# Sheet1.net
KiCad netlist of a schematic drawn in Altium Designer
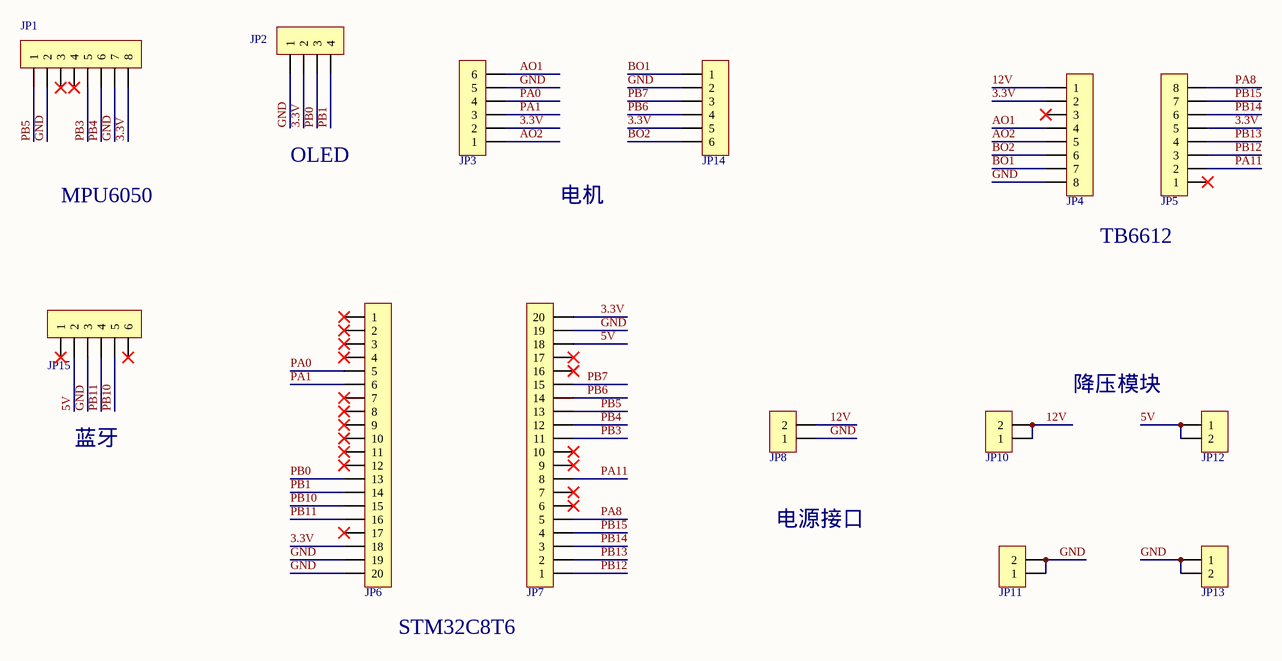
[diagram p0: Sheet1.SchDoc]

(export (version "E")
  (design (tool "Eeschema 10.0.6"))
  (components
    (comp (ref "JP1")
      (value "HDR-1X8")
      (footprint "HDR2.54-M-LI-8P")
      (description "8P接插件")
      (fields (field (name "版权归属") "封装库来自淘宝 ID：黄晶宝石"))
      (libsource (lib "5.3 - 接插件-脚距2.54 (100mil) ") (part "Header 8"))
    )
    (comp (ref "JP2")
      (value "HDR-1X4")
      (footprint "HDR2.54-M-LI-4P")
      (description "4P接插件")
      (fields (field (name "版权归属") "封装库来自淘宝 ID：黄晶宝石"))
      (libsource (lib "5.3 - 接插件-脚距2.54 (100mil) ") (part "Header 4"))
    )
    (comp (ref "JP3")
      (value "HDR-1X6")
      (footprint "HDR2.54-LI-6P")
      (description "6P接插件")
      (fields (field (name "版权归属") "封装库来自淘宝 ID：黄晶宝石"))
      (libsource (lib "5.3 - 接插件-脚距2.54 (100mil) ") (part "Header 6"))
    )
    (comp (ref "JP4")
      (value "HDR-1X8")
      (footprint "HDR2.54-M-LI-8P")
      (description "8P接插件")
      (fields (field (name "版权归属") "封装库来自淘宝 ID：黄晶宝石"))
      (libsource (lib "") (part "Header 8_2"))
    )
    (comp (ref "JP5")
      (value "HDR-1X8")
      (footprint "HDR2.54-M-LI-8P")
      (description "8P接插件")
      (fields (field (name "版权归属") "封装库来自淘宝 ID：黄晶宝石"))
      (libsource (lib "") (part "Header 8_1"))
    )
    (comp (ref "JP6")
      (value "HDR-1X20")
      (footprint "HDR2.54-M-LI-20P")
      (description "20P接插件")
      (fields (field (name "版权归属") "封装库来自淘宝 ID：黄晶宝石"))
      (libsource (lib "") (part "Header 20_1"))
    )
    (comp (ref "JP7")
      (value "HDR-1X20")
      (footprint "HDR2.54-M-LI-20P")
      (description "20P接插件")
      (fields (field (name "版权归属") "封装库来自淘宝 ID：黄晶宝石"))
      (libsource (lib "5.3 - 接插件-脚距2.54 (100mil) ") (part "Header 20"))
    )
    (comp (ref "JP8")
      (value "HDR-1X2")
      (footprint "HDR2.54-M-LI-2P")
      (description "2P接插件")
      (fields (field (name "版权归属") "封装库来自淘宝 ID：黄晶宝石"))
      (libsource (lib "5.3 - 接插件-脚距2.54 (100mil) ") (part "Header 2"))
    )
    (comp (ref "JP10")
      (value "HDR-1X2")
      (footprint "HDR2.54-M-LI-2P")
      (description "2P接插件")
      (fields (field (name "版权归属") "封装库来自淘宝 ID：黄晶宝石"))
      (libsource (lib "5.3 - 接插件-脚距2.54 (100mil) ") (part "Header 2"))
    )
    (comp (ref "JP11")
      (value "HDR-1X2")
      (footprint "HDR2.54-M-LI-2P")
      (description "2P接插件")
      (fields (field (name "版权归属") "封装库来自淘宝 ID：黄晶宝石"))
      (libsource (lib "5.3 - 接插件-脚距2.54 (100mil) ") (part "Header 2"))
    )
    (comp (ref "JP12")
      (value "HDR-1X2")
      (footprint "HDR2.54-M-LI-2P")
      (description "2P接插件")
      (fields (field (name "版权归属") "封装库来自淘宝 ID：黄晶宝石"))
      (libsource (lib "") (part "Header 2_1"))
    )
    (comp (ref "JP13")
      (value "HDR-1X2")
      (footprint "HDR2.54-M-LI-2P")
      (description "2P接插件")
      (fields (field (name "版权归属") "封装库来自淘宝 ID：黄晶宝石"))
      (libsource (lib "") (part "Header 2_1"))
    )
    (comp (ref "JP14")
      (value "HDR-1X6")
      (footprint "HDR2.54-LI-6P")
      (description "6P接插件")
      (fields (field (name "版权归属") "封装库来自淘宝 ID：黄晶宝石"))
      (libsource (lib "") (part "Header 6_2"))
    )
    (comp (ref "JP15")
      (value "HDR-1X6")
      (footprint "HDR2.54-LI-6P")
      (description "6P接插件")
      (fields (field (name "版权归属") "封装库来自淘宝 ID：黄晶宝石"))
      (libsource (lib "") (part "Header 6_1"))
    )
  )
  (nets
    (net (code "1") (name "/3.3V") (class "Default")
      (node (ref "JP1") (pin "8") (pinfunction "8_8") (pintype "passive"))
      (node (ref "JP14") (pin "5") (pinfunction "5_5") (pintype "passive"))
      (node (ref "JP2") (pin "2") (pinfunction "2_2") (pintype "passive"))
      (node (ref "JP3") (pin "2") (pinfunction "2_2") (pintype "passive"))
      (node (ref "JP4") (pin "2") (pinfunction "2_2") (pintype "passive"))
      (node (ref "JP5") (pin "5") (pinfunction "5_5") (pintype "passive"))
      (node (ref "JP6") (pin "18") (pinfunction "18_18") (pintype "passive"))
      (node (ref "JP7") (pin "20") (pinfunction "20_20") (pintype "passive"))
    )
    (net (code "2") (name "/5V") (class "Default")
      (node (ref "JP12") (pin "1") (pinfunction "1_1") (pintype "passive"))
      (node (ref "JP12") (pin "2") (pinfunction "2_2") (pintype "passive"))
      (node (ref "JP15") (pin "2") (pinfunction "2_2") (pintype "passive"))
      (node (ref "JP7") (pin "18") (pinfunction "18_18") (pintype "passive"))
    )
    (net (code "3") (name "/12V") (class "Default")
      (node (ref "JP10") (pin "1") (pinfunction "1_1") (pintype "passive"))
      (node (ref "JP10") (pin "2") (pinfunction "2_2") (pintype "passive"))
      (node (ref "JP4") (pin "1") (pinfunction "1_1") (pintype "passive"))
      (node (ref "JP8") (pin "2") (pinfunction "2_2") (pintype "passive"))
    )
    (net (code "4") (name "/AO1") (class "Default")
      (node (ref "JP3") (pin "6") (pinfunction "6_6") (pintype "passive"))
      (node (ref "JP4") (pin "4") (pinfunction "4_4") (pintype "passive"))
    )
    (net (code "5") (name "/AO2") (class "Default")
      (node (ref "JP3") (pin "1") (pinfunction "1_1") (pintype "passive"))
      (node (ref "JP4") (pin "5") (pinfunction "5_5") (pintype "passive"))
    )
    (net (code "6") (name "/BO1") (class "Default")
      (node (ref "JP14") (pin "1") (pinfunction "1_1") (pintype "passive"))
      (node (ref "JP4") (pin "7") (pinfunction "7_7") (pintype "passive"))
    )
    (net (code "7") (name "/BO2") (class "Default")
      (node (ref "JP14") (pin "6") (pinfunction "6_6") (pintype "passive"))
      (node (ref "JP4") (pin "6") (pinfunction "6_6") (pintype "passive"))
    )
    (net (code "8") (name "/GND") (class "Default")
      (node (ref "JP1") (pin "2") (pinfunction "2_2") (pintype "passive"))
      (node (ref "JP1") (pin "7") (pinfunction "7_7") (pintype "passive"))
      (node (ref "JP11") (pin "1") (pinfunction "1_1") (pintype "passive"))
      (node (ref "JP11") (pin "2") (pinfunction "2_2") (pintype "passive"))
      (node (ref "JP13") (pin "1") (pinfunction "1_1") (pintype "passive"))
      (node (ref "JP13") (pin "2") (pinfunction "2_2") (pintype "passive"))
      (node (ref "JP14") (pin "2") (pinfunction "2_2") (pintype "passive"))
      (node (ref "JP15") (pin "3") (pinfunction "3_3") (pintype "passive"))
      (node (ref "JP2") (pin "1") (pinfunction "1_1") (pintype "passive"))
      (node (ref "JP3") (pin "5") (pinfunction "5_5") (pintype "passive"))
      (node (ref "JP4") (pin "8") (pinfunction "8_8") (pintype "passive"))
      (node (ref "JP6") (pin "19") (pinfunction "19_19") (pintype "passive"))
      (node (ref "JP6") (pin "20") (pinfunction "20_20") (pintype "passive"))
      (node (ref "JP7") (pin "19") (pinfunction "19_19") (pintype "passive"))
      (node (ref "JP8") (pin "1") (pinfunction "1_1") (pintype "passive"))
    )
    (net (code "9") (name "/PA0") (class "Default")
      (node (ref "JP3") (pin "4") (pinfunction "4_4") (pintype "passive"))
      (node (ref "JP6") (pin "5") (pinfunction "5_5") (pintype "passive"))
    )
    (net (code "10") (name "/PA1") (class "Default")
      (node (ref "JP3") (pin "3") (pinfunction "3_3") (pintype "passive"))
      (node (ref "JP6") (pin "6") (pinfunction "6_6") (pintype "passive"))
    )
    (net (code "11") (name "/PA8") (class "Default")
      (node (ref "JP5") (pin "8") (pinfunction "8_8") (pintype "passive"))
      (node (ref "JP7") (pin "5") (pinfunction "5_5") (pintype "passive"))
    )
    (net (code "12") (name "/PA11") (class "Default")
      (node (ref "JP5") (pin "2") (pinfunction "2_2") (pintype "passive"))
      (node (ref "JP7") (pin "8") (pinfunction "8_8") (pintype "passive"))
    )
    (net (code "13") (name "/PB0") (class "Default")
      (node (ref "JP2") (pin "3") (pinfunction "3_3") (pintype "passive"))
      (node (ref "JP6") (pin "13") (pinfunction "13_13") (pintype "passive"))
    )
    (net (code "14") (name "/PB1") (class "Default")
      (node (ref "JP2") (pin "4") (pinfunction "4_4") (pintype "passive"))
      (node (ref "JP6") (pin "14") (pinfunction "14_14") (pintype "passive"))
    )
    (net (code "15") (name "/PB3") (class "Default")
      (node (ref "JP1") (pin "5") (pinfunction "5_5") (pintype "passive"))
      (node (ref "JP7") (pin "11") (pinfunction "11_11") (pintype "passive"))
    )
    (net (code "16") (name "/PB4") (class "Default")
      (node (ref "JP1") (pin "6") (pinfunction "6_6") (pintype "passive"))
      (node (ref "JP7") (pin "12") (pinfunction "12_12") (pintype "passive"))
    )
    (net (code "17") (name "/PB5") (class "Default")
      (node (ref "JP1") (pin "1") (pinfunction "1_1") (pintype "passive"))
      (node (ref "JP7") (pin "13") (pinfunction "13_13") (pintype "passive"))
    )
    (net (code "18") (name "/PB6") (class "Default")
      (node (ref "JP14") (pin "4") (pinfunction "4_4") (pintype "passive"))
      (node (ref "JP7") (pin "14") (pinfunction "14_14") (pintype "passive"))
    )
    (net (code "19") (name "/PB7") (class "Default")
      (node (ref "JP14") (pin "3") (pinfunction "3_3") (pintype "passive"))
      (node (ref "JP7") (pin "15") (pinfunction "15_15") (pintype "passive"))
    )
    (net (code "20") (name "/PB10") (class "Default")
      (node (ref "JP15") (pin "5") (pinfunction "5_5") (pintype "passive"))
      (node (ref "JP6") (pin "15") (pinfunction "15_15") (pintype "passive"))
    )
    (net (code "21") (name "/PB11") (class "Default")
      (node (ref "JP15") (pin "4") (pinfunction "4_4") (pintype "passive"))
      (node (ref "JP6") (pin "16") (pinfunction "16_16") (pintype "passive"))
    )
    (net (code "22") (name "/PB12") (class "Default")
      (node (ref "JP5") (pin "3") (pinfunction "3_3") (pintype "passive"))
      (node (ref "JP7") (pin "1") (pinfunction "1_1") (pintype "passive"))
    )
    (net (code "23") (name "/PB13") (class "Default")
      (node (ref "JP5") (pin "4") (pinfunction "4_4") (pintype "passive"))
      (node (ref "JP7") (pin "2") (pinfunction "2_2") (pintype "passive"))
    )
    (net (code "24") (name "/PB14") (class "Default")
      (node (ref "JP5") (pin "6") (pinfunction "6_6") (pintype "passive"))
      (node (ref "JP7") (pin "3") (pinfunction "3_3") (pintype "passive"))
    )
    (net (code "25") (name "/PB15") (class "Default")
      (node (ref "JP5") (pin "7") (pinfunction "7_7") (pintype "passive"))
      (node (ref "JP7") (pin "4") (pinfunction "4_4") (pintype "passive"))
    )
    (net (code "26") (name "unconnected-(JP1-Pad3)") (class "Default")
      (node (ref "JP1") (pin "3") (pinfunction "3_3") (pintype "passive+no_connect"))
    )
    (net (code "27") (name "unconnected-(JP1-Pad4)") (class "Default")
      (node (ref "JP1") (pin "4") (pinfunction "4_4") (pintype "passive+no_connect"))
    )
    (net (code "28") (name "unconnected-(JP4-Pad3)") (class "Default")
      (node (ref "JP4") (pin "3") (pinfunction "3_3") (pintype "passive+no_connect"))
    )
    (net (code "29") (name "unconnected-(JP5-Pad1)") (class "Default")
      (node (ref "JP5") (pin "1") (pinfunction "1_1") (pintype "passive+no_connect"))
    )
    (net (code "30") (name "unconnected-(JP6-Pad1)") (class "Default")
      (node (ref "JP6") (pin "1") (pinfunction "1_1") (pintype "passive+no_connect"))
    )
    (net (code "31") (name "unconnected-(JP6-Pad2)") (class "Default")
      (node (ref "JP6") (pin "2") (pinfunction "2_2") (pintype "passive+no_connect"))
    )
    (net (code "32") (name "unconnected-(JP6-Pad3)") (class "Default")
      (node (ref "JP6") (pin "3") (pinfunction "3_3") (pintype "passive+no_connect"))
    )
    (net (code "33") (name "unconnected-(JP6-Pad4)") (class "Default")
      (node (ref "JP6") (pin "4") (pinfunction "4_4") (pintype "passive+no_connect"))
    )
    (net (code "34") (name "unconnected-(JP6-Pad7)") (class "Default")
      (node (ref "JP6") (pin "7") (pinfunction "7_7") (pintype "passive+no_connect"))
    )
    (net (code "35") (name "unconnected-(JP6-Pad8)") (class "Default")
      (node (ref "JP6") (pin "8") (pinfunction "8_8") (pintype "passive+no_connect"))
    )
    (net (code "36") (name "unconnected-(JP6-Pad9)") (class "Default")
      (node (ref "JP6") (pin "9") (pinfunction "9_9") (pintype "passive+no_connect"))
    )
    (net (code "37") (name "unconnected-(JP6-Pad10)") (class "Default")
      (node (ref "JP6") (pin "10") (pinfunction "10_10") (pintype "passive+no_connect"))
    )
    (net (code "38") (name "unconnected-(JP6-Pad11)") (class "Default")
      (node (ref "JP6") (pin "11") (pinfunction "11_11") (pintype "passive+no_connect"))
    )
    (net (code "39") (name "unconnected-(JP6-Pad12)") (class "Default")
      (node (ref "JP6") (pin "12") (pinfunction "12_12") (pintype "passive+no_connect"))
    )
    (net (code "40") (name "unconnected-(JP6-Pad17)") (class "Default")
      (node (ref "JP6") (pin "17") (pinfunction "17_17") (pintype "passive+no_connect"))
    )
    (net (code "41") (name "unconnected-(JP7-Pad6)") (class "Default")
      (node (ref "JP7") (pin "6") (pinfunction "6_6") (pintype "passive+no_connect"))
    )
    (net (code "42") (name "unconnected-(JP7-Pad7)") (class "Default")
      (node (ref "JP7") (pin "7") (pinfunction "7_7") (pintype "passive+no_connect"))
    )
    (net (code "43") (name "unconnected-(JP7-Pad9)") (class "Default")
      (node (ref "JP7") (pin "9") (pinfunction "9_9") (pintype "passive+no_connect"))
    )
    (net (code "44") (name "unconnected-(JP7-Pad10)") (class "Default")
      (node (ref "JP7") (pin "10") (pinfunction "10_10") (pintype "passive+no_connect"))
    )
    (net (code "45") (name "unconnected-(JP7-Pad16)") (class "Default")
      (node (ref "JP7") (pin "16") (pinfunction "16_16") (pintype "passive+no_connect"))
    )
    (net (code "46") (name "unconnected-(JP7-Pad17)") (class "Default")
      (node (ref "JP7") (pin "17") (pinfunction "17_17") (pintype "passive+no_connect"))
    )
    (net (code "47") (name "unconnected-(JP15-Pad1)") (class "Default")
      (node (ref "JP15") (pin "1") (pinfunction "1_1") (pintype "passive+no_connect"))
    )
    (net (code "48") (name "unconnected-(JP15-Pad6)") (class "Default")
      (node (ref "JP15") (pin "6") (pinfunction "6_6") (pintype "passive+no_connect"))
    )
  )
)
